# Regulator.net
KiCad netlist of a schematic drawn in Altium Designer
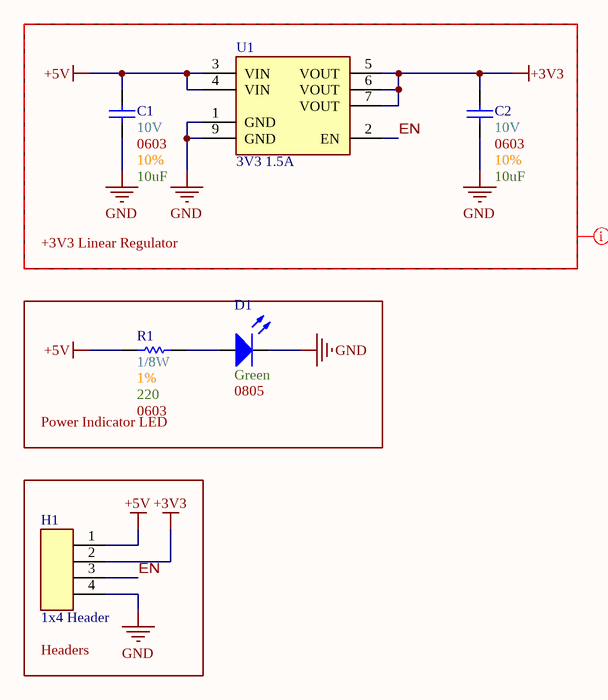
[diagram p0: Regulator.SchDoc]

(export (version "E")
  (design (tool "Eeschema 10.0.6"))
  (components
    (comp (ref "C1")
      (value "[Cap] 0603 10uF 10% 10V")
      (footprint "[Cap] SMD 0603")
      (description "CL10A106KP8NNNC")
      (fields
        (field (name "MAX VOLTAGE") "10V")
        (field (name "SIZE PACKAGE") "0603")
        (field (name "TOLERANCE") "10%")
        (field (name "CAPACITANCE") "10uF")
      )
      (libsource (lib "Capacitors") (part "[Cap] 0603 10uF 10% 10V"))
    )
    (comp (ref "C2")
      (value "[Cap] 0603 10uF 10% 10V")
      (footprint "[Cap] SMD 0603")
      (description "CL10A106KP8NNNC")
      (fields
        (field (name "MAX VOLTAGE") "10V")
        (field (name "SIZE PACKAGE") "0603")
        (field (name "TOLERANCE") "10%")
        (field (name "CAPACITANCE") "10uF")
      )
      (libsource (lib "Capacitors") (part "[Cap] 0603 10uF 10% 10V"))
    )
    (comp (ref "D1")
      (value "[LED] SMD 0805 Green")
      (footprint "[LED] SMD 0805")
      (description "LG R971-KN-1-0-20-R18")
      (fields (field (name "COLOR") "Green") (field (name "SIZE PACKAGE") "0805"))
      (libsource (lib "LEDs") (part "[LED] SMD 0805 Green"))
    )
    (comp (ref "H1")
      (value "1x4 Header")
      (footprint "[Header] 1x4 Male")
      (description "2.54mm pitch")
      (libsource (lib "Connectors") (part "[Header] 1x4 Male"))
    )
    (comp (ref "R1")
      (value "[220] SMD 0603 1% 1/10W")
      (footprint "[Res] SMD 0603")
      (description "CRGCQ0805F220R")
      (fields
        (field (name "WATTAGE") "1/8W")
        (field (name "TOLERANCE") "1%")
        (field (name "RESISTANCE") "220")
        (field (name "SIZE PACKAGE") "0603")
      )
      (libsource (lib "Resistors") (part "[220] SMD 0603 1% 1/10W"))
    )
    (comp (ref "U1")
      (value "3V3 1.5A")
      (footprint "[Linear] 3V3 1.5A")
      (description "AP7362A-33SP-13")
      (libsource (lib "Voltage Regulators") (part "[Linear] 3V3 1.5A"))
    )
  )
  (nets
    (net (code "1") (name "+3V3") (class "Default")
      (node (ref "C2") (pin "2") (pinfunction "2_2") (pintype "passive"))
      (node (ref "H1") (pin "2") (pintype "passive"))
      (node (ref "U1") (pin "5") (pinfunction "VOUT_5") (pintype "passive"))
      (node (ref "U1") (pin "6") (pinfunction "VOUT_6") (pintype "passive"))
      (node (ref "U1") (pin "7") (pinfunction "VOUT_7") (pintype "passive"))
    )
    (net (code "2") (name "+5V") (class "Default")
      (node (ref "C1") (pin "2") (pinfunction "2_2") (pintype "passive"))
      (node (ref "H1") (pin "1") (pintype "passive"))
      (node (ref "R1") (pin "1") (pinfunction "1_1") (pintype "passive"))
      (node (ref "U1") (pin "3") (pinfunction "VIN_3") (pintype "passive"))
      (node (ref "U1") (pin "4") (pinfunction "VIN_4") (pintype "passive"))
    )
    (net (code "3") (name "/EN") (class "Default")
      (node (ref "H1") (pin "3") (pintype "passive"))
      (node (ref "U1") (pin "2") (pinfunction "EN_2") (pintype "passive"))
    )
    (net (code "4") (name "GND") (class "Default")
      (node (ref "C1") (pin "1") (pinfunction "1_1") (pintype "passive"))
      (node (ref "C2") (pin "1") (pinfunction "1_1") (pintype "passive"))
      (node (ref "D1") (pin "2") (pinfunction "Cathode_2") (pintype "passive"))
      (node (ref "H1") (pin "4") (pintype "passive"))
      (node (ref "U1") (pin "1") (pinfunction "GND_1") (pintype "passive"))
      (node (ref "U1") (pin "9") (pinfunction "GND_9") (pintype "passive"))
    )
    (net (code "5") (name "Net-(D1-Anode)") (class "Default")
      (node (ref "D1") (pin "1") (pinfunction "Anode_1") (pintype "passive"))
      (node (ref "R1") (pin "2") (pinfunction "2_2") (pintype "passive"))
    )
  )
)
